# dotstar4.net
KiCad netlist of a schematic drawn in EAGLE
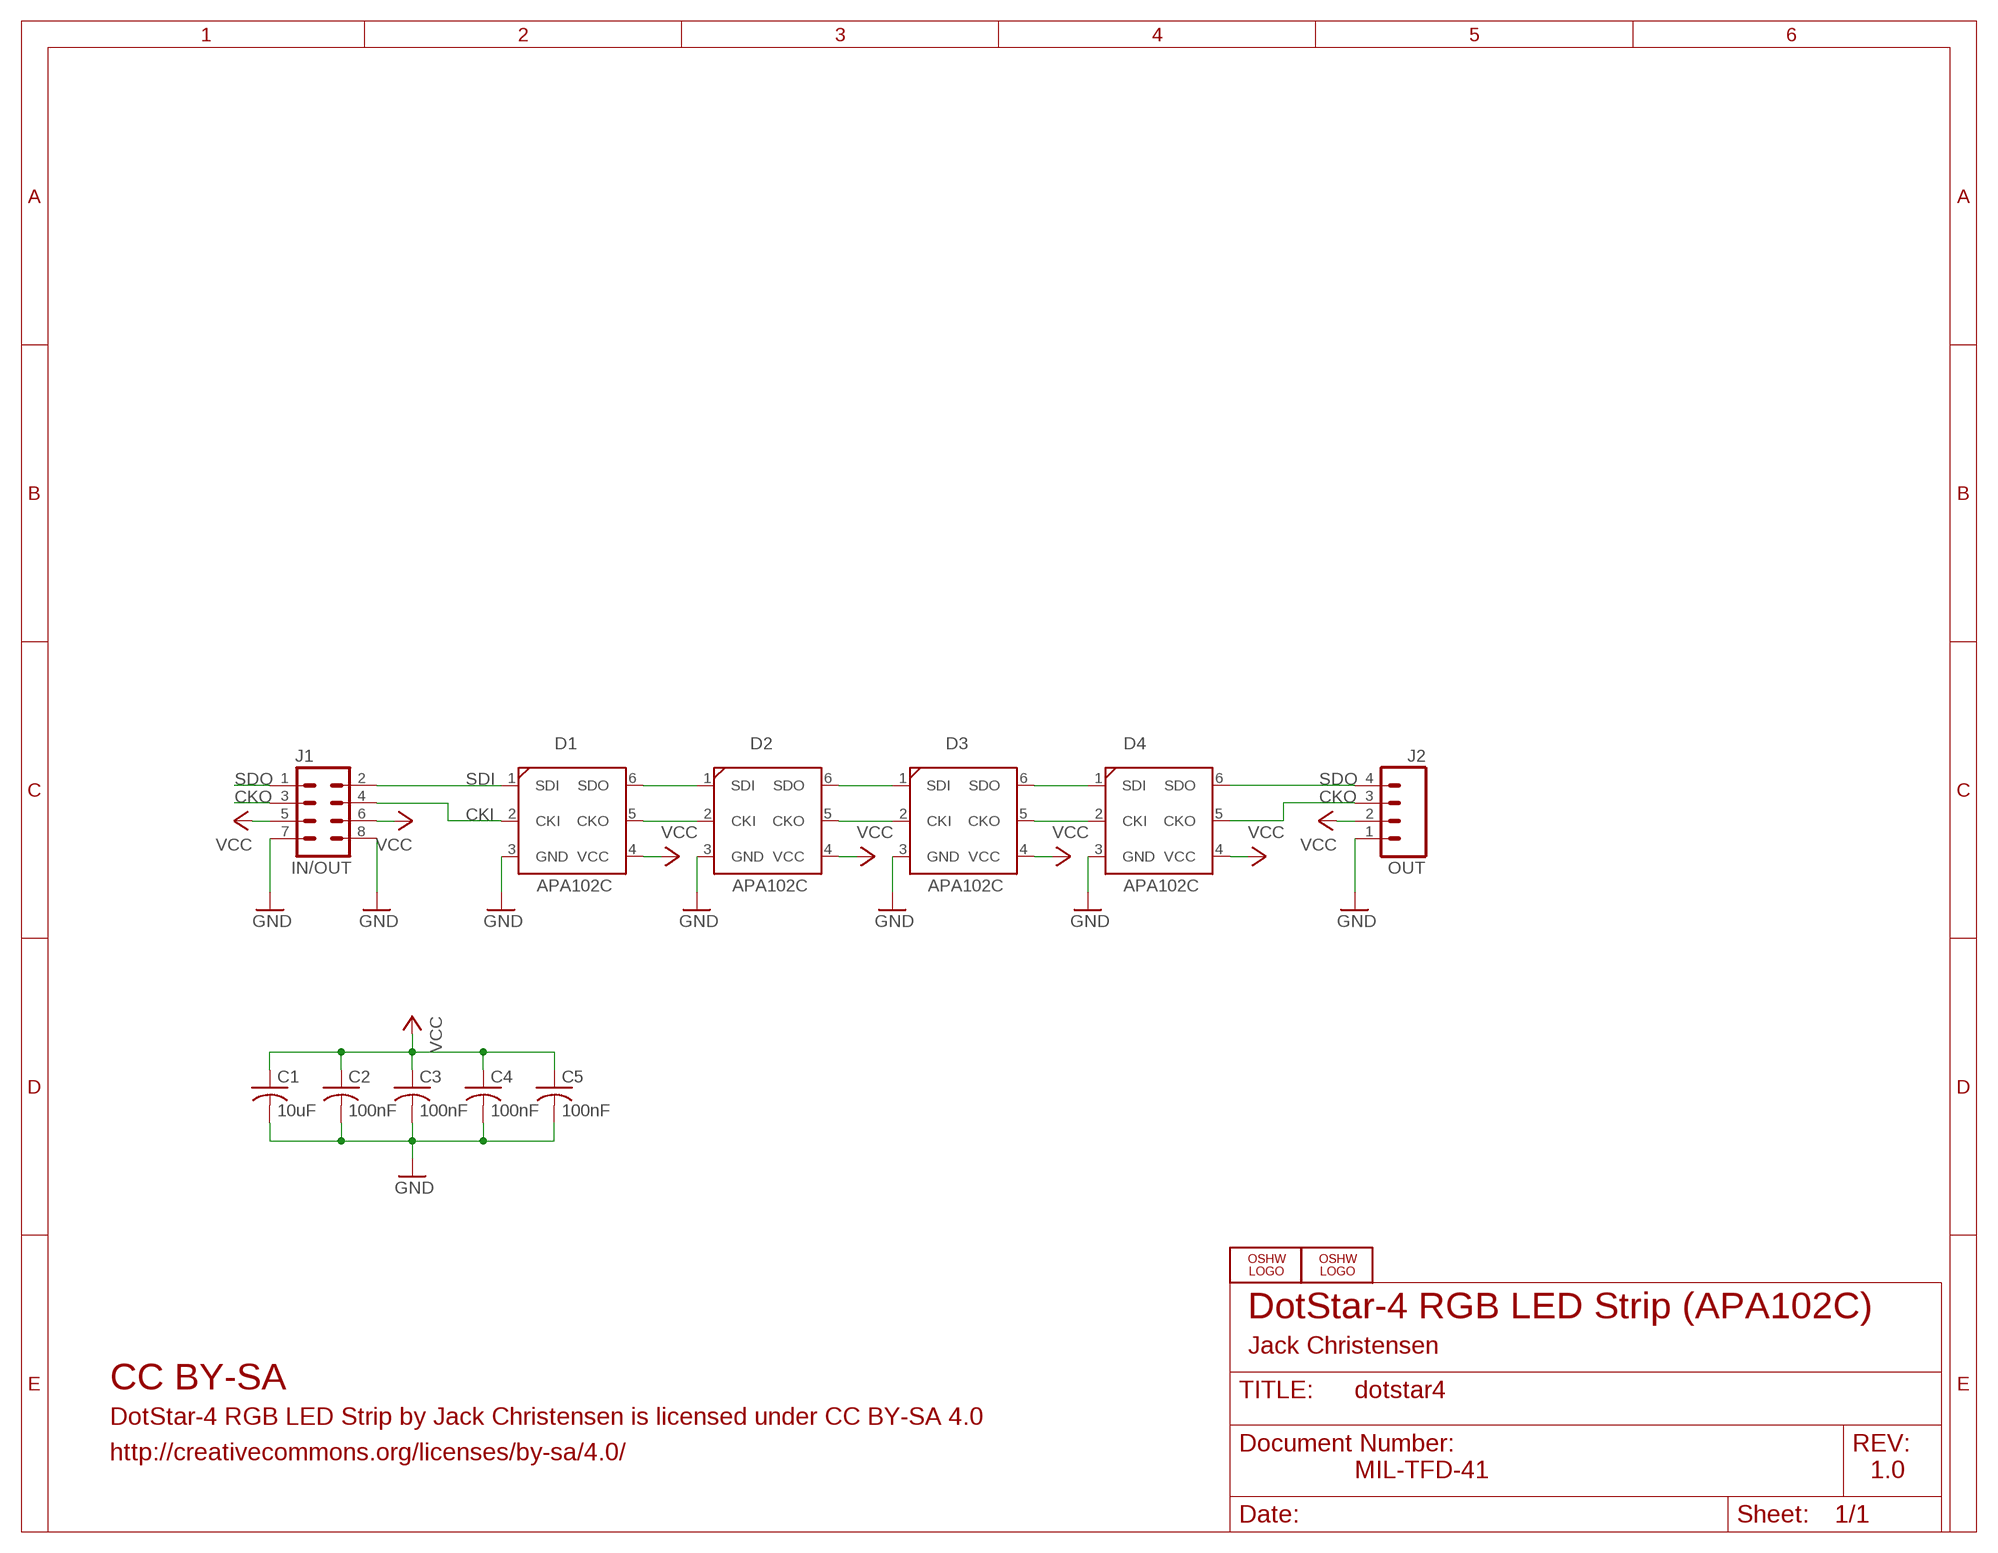
[diagram p0: schematic, sheet 1]

(export (version "E")
  (design (tool "Eeschema 10.0.6"))
  (components
    (comp (ref "C1")
      (value "10uF")
      (footprint "eagle-import:M0805")
      (libsource (lib "eagle-import") (part "C-USM0805"))
    )
    (comp (ref "C2")
      (value "100nF")
      (footprint "eagle-import:M0805")
      (libsource (lib "eagle-import") (part "C-USM0805"))
    )
    (comp (ref "C3")
      (value "100nF")
      (footprint "eagle-import:M0805")
      (libsource (lib "eagle-import") (part "C-USM0805"))
    )
    (comp (ref "C4")
      (value "100nF")
      (footprint "eagle-import:M0805")
      (libsource (lib "eagle-import") (part "C-USM0805"))
    )
    (comp (ref "C5")
      (value "100nF")
      (footprint "eagle-import:M0805")
      (libsource (lib "eagle-import") (part "C-USM0805"))
    )
    (comp (ref "D1")
      (value "APA102C")
      (footprint "eagle-import:RGB5050")
      (libsource (lib "eagle-import") (part "APA102C"))
    )
    (comp (ref "D2")
      (value "APA102C")
      (footprint "eagle-import:RGB5050")
      (libsource (lib "eagle-import") (part "APA102C"))
    )
    (comp (ref "D3")
      (value "APA102C")
      (footprint "eagle-import:RGB5050")
      (libsource (lib "eagle-import") (part "APA102C"))
    )
    (comp (ref "D4")
      (value "APA102C")
      (footprint "eagle-import:RGB5050")
      (libsource (lib "eagle-import") (part "APA102C"))
    )
    (comp (ref "J1")
      (value "IN/OUT")
      (footprint "eagle-import:2X4")
      (libsource (lib "eagle-import") (part "M04X2"))
    )
    (comp (ref "J2")
      (value "OUT")
      (footprint "eagle-import:1X04")
      (libsource (lib "eagle-import") (part "M04PTH"))
    )
    (comp (ref "LOGO1")
      (value "OSHW_LOGO_8MILX0150-NT")
      (footprint "eagle-import:OSHW_8X150_NOTEXT")
      (libsource (lib "eagle-import") (part "OSHW_LOGO_8MILX0150-NT"))
    )
    (comp (ref "LOGO2")
      (value "OSHW_LOGO_8MILX0150-NT")
      (footprint "eagle-import:OSHW_8X150_NOTEXT")
      (libsource (lib "eagle-import") (part "OSHW_LOGO_8MILX0150-NT"))
    )
  )
  (nets
    (net (code "1") (name "/CKI") (class "Default")
      (node (ref "D1") (pin "2") (pinfunction "CKI_2") (pintype "bidirectional"))
      (node (ref "J1") (pin "4") (pinfunction "4_4") (pintype "passive"))
    )
    (net (code "2") (name "/CKO") (class "Default")
      (node (ref "D4") (pin "5") (pinfunction "CKO_5") (pintype "bidirectional"))
      (node (ref "J1") (pin "3") (pinfunction "3_3") (pintype "passive"))
      (node (ref "J2") (pin "3") (pinfunction "3_3") (pintype "passive"))
    )
    (net (code "3") (name "/SDI") (class "Default")
      (node (ref "D1") (pin "1") (pinfunction "SDI_1") (pintype "bidirectional"))
      (node (ref "J1") (pin "2") (pinfunction "2_2") (pintype "passive"))
    )
    (net (code "4") (name "/SDO") (class "Default")
      (node (ref "D4") (pin "6") (pinfunction "SDO_6") (pintype "bidirectional"))
      (node (ref "J1") (pin "1") (pinfunction "1_1") (pintype "passive"))
      (node (ref "J2") (pin "4") (pinfunction "4_4") (pintype "passive"))
    )
    (net (code "5") (name "GND") (class "Default")
      (node (ref "C1") (pin "2") (pinfunction "2_2") (pintype "passive"))
      (node (ref "C2") (pin "2") (pinfunction "2_2") (pintype "passive"))
      (node (ref "C3") (pin "2") (pinfunction "2_2") (pintype "passive"))
      (node (ref "C4") (pin "2") (pinfunction "2_2") (pintype "passive"))
      (node (ref "C5") (pin "2") (pinfunction "2_2") (pintype "passive"))
      (node (ref "D1") (pin "3") (pinfunction "GND_3") (pintype "power_in"))
      (node (ref "D2") (pin "3") (pinfunction "GND_3") (pintype "power_in"))
      (node (ref "D3") (pin "3") (pinfunction "GND_3") (pintype "power_in"))
      (node (ref "D4") (pin "3") (pinfunction "GND_3") (pintype "power_in"))
      (node (ref "J1") (pin "7") (pinfunction "7_7") (pintype "passive"))
      (node (ref "J1") (pin "8") (pinfunction "8_8") (pintype "passive"))
      (node (ref "J2") (pin "1") (pinfunction "1_1") (pintype "passive"))
    )
    (net (code "6") (name "Net-(D1-CKO)") (class "Default")
      (node (ref "D1") (pin "5") (pinfunction "CKO_5") (pintype "bidirectional"))
      (node (ref "D2") (pin "2") (pinfunction "CKI_2") (pintype "bidirectional"))
    )
    (net (code "7") (name "Net-(D1-SDO)") (class "Default")
      (node (ref "D1") (pin "6") (pinfunction "SDO_6") (pintype "bidirectional"))
      (node (ref "D2") (pin "1") (pinfunction "SDI_1") (pintype "bidirectional"))
    )
    (net (code "8") (name "Net-(D2-CKO)") (class "Default")
      (node (ref "D2") (pin "5") (pinfunction "CKO_5") (pintype "bidirectional"))
      (node (ref "D3") (pin "2") (pinfunction "CKI_2") (pintype "bidirectional"))
    )
    (net (code "9") (name "Net-(D2-SDO)") (class "Default")
      (node (ref "D2") (pin "6") (pinfunction "SDO_6") (pintype "bidirectional"))
      (node (ref "D3") (pin "1") (pinfunction "SDI_1") (pintype "bidirectional"))
    )
    (net (code "10") (name "Net-(D3-CKO)") (class "Default")
      (node (ref "D3") (pin "5") (pinfunction "CKO_5") (pintype "bidirectional"))
      (node (ref "D4") (pin "2") (pinfunction "CKI_2") (pintype "bidirectional"))
    )
    (net (code "11") (name "Net-(D3-SDO)") (class "Default")
      (node (ref "D3") (pin "6") (pinfunction "SDO_6") (pintype "bidirectional"))
      (node (ref "D4") (pin "1") (pinfunction "SDI_1") (pintype "bidirectional"))
    )
    (net (code "12") (name "VCC") (class "Default")
      (node (ref "C1") (pin "1") (pinfunction "1_1") (pintype "passive"))
      (node (ref "C2") (pin "1") (pinfunction "1_1") (pintype "passive"))
      (node (ref "C3") (pin "1") (pinfunction "1_1") (pintype "passive"))
      (node (ref "C4") (pin "1") (pinfunction "1_1") (pintype "passive"))
      (node (ref "C5") (pin "1") (pinfunction "1_1") (pintype "passive"))
      (node (ref "D1") (pin "4") (pinfunction "VCC_4") (pintype "power_in"))
      (node (ref "D2") (pin "4") (pinfunction "VCC_4") (pintype "power_in"))
      (node (ref "D3") (pin "4") (pinfunction "VCC_4") (pintype "power_in"))
      (node (ref "D4") (pin "4") (pinfunction "VCC_4") (pintype "power_in"))
      (node (ref "J1") (pin "5") (pinfunction "5_5") (pintype "passive"))
      (node (ref "J1") (pin "6") (pinfunction "6_6") (pintype "passive"))
      (node (ref "J2") (pin "2") (pinfunction "2_2") (pintype "passive"))
    )
  )
)
